# MGNGSQ4_Extender.net
KiCad netlist of a schematic drawn in Altium Designer
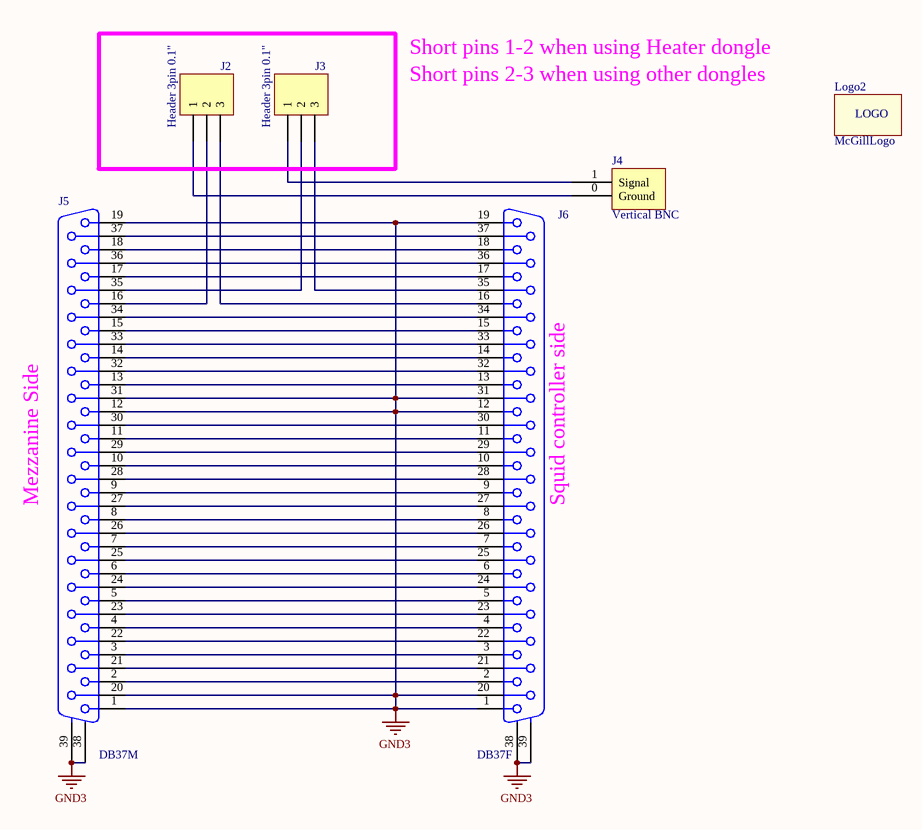
[diagram p0: MGNGSQ4_Extender.SchDoc]

(export (version "E")
  (design (tool "Eeschema 10.0.6"))
  (components
    (comp (ref "J2")
      (value "Header 3pin 0.1\"")
      (footprint "HDR1X3")
      (description "Header, 0.1\", 3-Pin straight")
      (fields
        (field (name "MANUFACTURER") "Digikey")
        (field (name "MANUFACTURER PART NUMBER") "961103-6404-AR")
      )
      (libsource (lib "MGNGSQ4_Dongles") (part "Header3"))
    )
    (comp (ref "J3")
      (value "Header 3pin 0.1\"")
      (footprint "HDR1X3")
      (description "Header, 0.1\", 3-Pin straight")
      (fields
        (field (name "MANUFACTURER") "Digikey")
        (field (name "MANUFACTURER PART NUMBER") "961103-6404-AR")
      )
      (libsource (lib "MGNGSQ4_Dongles") (part "Header3"))
    )
    (comp (ref "J4")
      (value "Vertical BNC")
      (footprint "BNCVert")
      (fields
        (field (name "MANUFACTURER") "TE Connectivity AMP Connectors")
        (field (name "MANUFACTURER PART NUMBER") "5-1634503-1")
      )
      (libsource (lib "MGNGSQ4_Dongles") (part "BNCVertical"))
    )
    (comp (ref "J5")
      (value "DB37M")
      (footprint "DSUB37-M")
      (fields
        (field (name "MANUFACTURER") "Norcomp")
        (field (name "MANUFACTURER PART NUMBER") "182-037-113R531")
      )
      (libsource (lib "MGNGSQ4_Dongles") (part "DB37M"))
    )
    (comp (ref "J6")
      (value "DB37F")
      (footprint "DSUB37-F")
      (fields
        (field (name "MANUFACTURER") "Norcomp")
        (field (name "MANUFACTURER PART NUMBER") "182-037-213R181")
      )
      (libsource (lib "MGNGSQ4_Dongles") (part "DB37F"))
    )
    (comp (ref "Logo2")
      (value "McGillLogo")
      (footprint "McGillLogo1")
      (description "Silkscreen Logo")
      (fields (field (name "MANUFACTURER") "McGill"))
      (libsource (lib "MGMEZZ04_Loopback") (part "Logo"))
    )
  )
  (nets
    (net (code "1") (name "GND3") (class "Default")
      (node (ref "J5") (pin "1") (pinfunction "1_1") (pintype "passive"))
      (node (ref "J5") (pin "12") (pinfunction "12_12") (pintype "passive"))
      (node (ref "J5") (pin "19") (pinfunction "19_19") (pintype "passive"))
      (node (ref "J5") (pin "20") (pinfunction "20_20") (pintype "passive"))
      (node (ref "J5") (pin "31") (pinfunction "31_31") (pintype "passive"))
      (node (ref "J5") (pin "38") (pinfunction "MH1_38") (pintype "passive"))
      (node (ref "J5") (pin "39") (pinfunction "MH2_39") (pintype "passive"))
      (node (ref "J6") (pin "1") (pinfunction "1_1") (pintype "passive"))
      (node (ref "J6") (pin "12") (pinfunction "12_12") (pintype "passive"))
      (node (ref "J6") (pin "19") (pinfunction "19_19") (pintype "passive"))
      (node (ref "J6") (pin "20") (pinfunction "20_20") (pintype "passive"))
      (node (ref "J6") (pin "31") (pinfunction "31_31") (pintype "passive"))
      (node (ref "J6") (pin "38") (pinfunction "MH1_38") (pintype "passive"))
      (node (ref "J6") (pin "39") (pinfunction "MH2_39") (pintype "passive"))
    )
    (net (code "2") (name "Net-(J2-Pad2)") (class "Default")
      (node (ref "J2") (pin "2") (pinfunction "2_2") (pintype "passive"))
      (node (ref "J5") (pin "16") (pinfunction "16_16") (pintype "passive"))
    )
    (net (code "3") (name "Net-(J2-Pad3)") (class "Default")
      (node (ref "J2") (pin "3") (pinfunction "3_3") (pintype "passive"))
      (node (ref "J6") (pin "16") (pinfunction "16_16") (pintype "passive"))
    )
    (net (code "4") (name "Net-(J3-Pad2)") (class "Default")
      (node (ref "J3") (pin "2") (pinfunction "2_2") (pintype "passive"))
      (node (ref "J5") (pin "35") (pinfunction "35_35") (pintype "passive"))
    )
    (net (code "5") (name "Net-(J3-Pad3)") (class "Default")
      (node (ref "J3") (pin "3") (pinfunction "3_3") (pintype "passive"))
      (node (ref "J6") (pin "35") (pinfunction "35_35") (pintype "passive"))
    )
    (net (code "6") (name "Net-(J4-Ground)") (class "Default")
      (node (ref "J2") (pin "1") (pinfunction "1_1") (pintype "passive"))
      (node (ref "J4") (pin "0") (pinfunction "Ground_0") (pintype "passive"))
    )
    (net (code "7") (name "Net-(J4-Signal)") (class "Default")
      (node (ref "J3") (pin "1") (pinfunction "1_1") (pintype "passive"))
      (node (ref "J4") (pin "1") (pinfunction "Signal_1") (pintype "passive"))
    )
    (net (code "8") (name "Net-(J5-Pad2)") (class "Default")
      (node (ref "J5") (pin "2") (pinfunction "2_2") (pintype "passive"))
      (node (ref "J6") (pin "2") (pinfunction "2_2") (pintype "passive"))
    )
    (net (code "9") (name "Net-(J5-Pad3)") (class "Default")
      (node (ref "J5") (pin "3") (pinfunction "3_3") (pintype "passive"))
      (node (ref "J6") (pin "3") (pinfunction "3_3") (pintype "passive"))
    )
    (net (code "10") (name "Net-(J5-Pad4)") (class "Default")
      (node (ref "J5") (pin "4") (pinfunction "4_4") (pintype "passive"))
      (node (ref "J6") (pin "4") (pinfunction "4_4") (pintype "passive"))
    )
    (net (code "11") (name "Net-(J5-Pad5)") (class "Default")
      (node (ref "J5") (pin "5") (pinfunction "5_5") (pintype "passive"))
      (node (ref "J6") (pin "5") (pinfunction "5_5") (pintype "passive"))
    )
    (net (code "12") (name "Net-(J5-Pad6)") (class "Default")
      (node (ref "J5") (pin "6") (pinfunction "6_6") (pintype "passive"))
      (node (ref "J6") (pin "6") (pinfunction "6_6") (pintype "passive"))
    )
    (net (code "13") (name "Net-(J5-Pad7)") (class "Default")
      (node (ref "J5") (pin "7") (pinfunction "7_7") (pintype "passive"))
      (node (ref "J6") (pin "7") (pinfunction "7_7") (pintype "passive"))
    )
    (net (code "14") (name "Net-(J5-Pad8)") (class "Default")
      (node (ref "J5") (pin "8") (pinfunction "8_8") (pintype "passive"))
      (node (ref "J6") (pin "8") (pinfunction "8_8") (pintype "passive"))
    )
    (net (code "15") (name "Net-(J5-Pad9)") (class "Default")
      (node (ref "J5") (pin "9") (pinfunction "9_9") (pintype "passive"))
      (node (ref "J6") (pin "9") (pinfunction "9_9") (pintype "passive"))
    )
    (net (code "16") (name "Net-(J5-Pad10)") (class "Default")
      (node (ref "J5") (pin "10") (pinfunction "10_10") (pintype "passive"))
      (node (ref "J6") (pin "10") (pinfunction "10_10") (pintype "passive"))
    )
    (net (code "17") (name "Net-(J5-Pad11)") (class "Default")
      (node (ref "J5") (pin "11") (pinfunction "11_11") (pintype "passive"))
      (node (ref "J6") (pin "11") (pinfunction "11_11") (pintype "passive"))
    )
    (net (code "18") (name "Net-(J5-Pad13)") (class "Default")
      (node (ref "J5") (pin "13") (pinfunction "13_13") (pintype "passive"))
      (node (ref "J6") (pin "13") (pinfunction "13_13") (pintype "passive"))
    )
    (net (code "19") (name "Net-(J5-Pad14)") (class "Default")
      (node (ref "J5") (pin "14") (pinfunction "14_14") (pintype "passive"))
      (node (ref "J6") (pin "14") (pinfunction "14_14") (pintype "passive"))
    )
    (net (code "20") (name "Net-(J5-Pad15)") (class "Default")
      (node (ref "J5") (pin "15") (pinfunction "15_15") (pintype "passive"))
      (node (ref "J6") (pin "15") (pinfunction "15_15") (pintype "passive"))
    )
    (net (code "21") (name "Net-(J5-Pad17)") (class "Default")
      (node (ref "J5") (pin "17") (pinfunction "17_17") (pintype "passive"))
      (node (ref "J6") (pin "17") (pinfunction "17_17") (pintype "passive"))
    )
    (net (code "22") (name "Net-(J5-Pad18)") (class "Default")
      (node (ref "J5") (pin "18") (pinfunction "18_18") (pintype "passive"))
      (node (ref "J6") (pin "18") (pinfunction "18_18") (pintype "passive"))
    )
    (net (code "23") (name "Net-(J5-Pad21)") (class "Default")
      (node (ref "J5") (pin "21") (pinfunction "21_21") (pintype "passive"))
      (node (ref "J6") (pin "21") (pinfunction "21_21") (pintype "passive"))
    )
    (net (code "24") (name "Net-(J5-Pad22)") (class "Default")
      (node (ref "J5") (pin "22") (pinfunction "22_22") (pintype "passive"))
      (node (ref "J6") (pin "22") (pinfunction "22_22") (pintype "passive"))
    )
    (net (code "25") (name "Net-(J5-Pad23)") (class "Default")
      (node (ref "J5") (pin "23") (pinfunction "23_23") (pintype "passive"))
      (node (ref "J6") (pin "23") (pinfunction "23_23") (pintype "passive"))
    )
    (net (code "26") (name "Net-(J5-Pad24)") (class "Default")
      (node (ref "J5") (pin "24") (pinfunction "24_24") (pintype "passive"))
      (node (ref "J6") (pin "24") (pinfunction "24_24") (pintype "passive"))
    )
    (net (code "27") (name "Net-(J5-Pad25)") (class "Default")
      (node (ref "J5") (pin "25") (pinfunction "25_25") (pintype "passive"))
      (node (ref "J6") (pin "25") (pinfunction "25_25") (pintype "passive"))
    )
    (net (code "28") (name "Net-(J5-Pad26)") (class "Default")
      (node (ref "J5") (pin "26") (pinfunction "26_26") (pintype "passive"))
      (node (ref "J6") (pin "26") (pinfunction "26_26") (pintype "passive"))
    )
    (net (code "29") (name "Net-(J5-Pad27)") (class "Default")
      (node (ref "J5") (pin "27") (pinfunction "27_27") (pintype "passive"))
      (node (ref "J6") (pin "27") (pinfunction "27_27") (pintype "passive"))
    )
    (net (code "30") (name "Net-(J5-Pad28)") (class "Default")
      (node (ref "J5") (pin "28") (pinfunction "28_28") (pintype "passive"))
      (node (ref "J6") (pin "28") (pinfunction "28_28") (pintype "passive"))
    )
    (net (code "31") (name "Net-(J5-Pad29)") (class "Default")
      (node (ref "J5") (pin "29") (pinfunction "29_29") (pintype "passive"))
      (node (ref "J6") (pin "29") (pinfunction "29_29") (pintype "passive"))
    )
    (net (code "32") (name "Net-(J5-Pad30)") (class "Default")
      (node (ref "J5") (pin "30") (pinfunction "30_30") (pintype "passive"))
      (node (ref "J6") (pin "30") (pinfunction "30_30") (pintype "passive"))
    )
    (net (code "33") (name "Net-(J5-Pad32)") (class "Default")
      (node (ref "J5") (pin "32") (pinfunction "32_32") (pintype "passive"))
      (node (ref "J6") (pin "32") (pinfunction "32_32") (pintype "passive"))
    )
    (net (code "34") (name "Net-(J5-Pad33)") (class "Default")
      (node (ref "J5") (pin "33") (pinfunction "33_33") (pintype "passive"))
      (node (ref "J6") (pin "33") (pinfunction "33_33") (pintype "passive"))
    )
    (net (code "35") (name "Net-(J5-Pad34)") (class "Default")
      (node (ref "J5") (pin "34") (pinfunction "34_34") (pintype "passive"))
      (node (ref "J6") (pin "34") (pinfunction "34_34") (pintype "passive"))
    )
    (net (code "36") (name "Net-(J5-Pad36)") (class "Default")
      (node (ref "J5") (pin "36") (pinfunction "36_36") (pintype "passive"))
      (node (ref "J6") (pin "36") (pinfunction "36_36") (pintype "passive"))
    )
    (net (code "37") (name "Net-(J5-Pad37)") (class "Default")
      (node (ref "J5") (pin "37") (pinfunction "37_37") (pintype "passive"))
      (node (ref "J6") (pin "37") (pinfunction "37_37") (pintype "passive"))
    )
  )
)
